# etf_pwr.net
KiCad netlist of a schematic drawn in Altium Designer
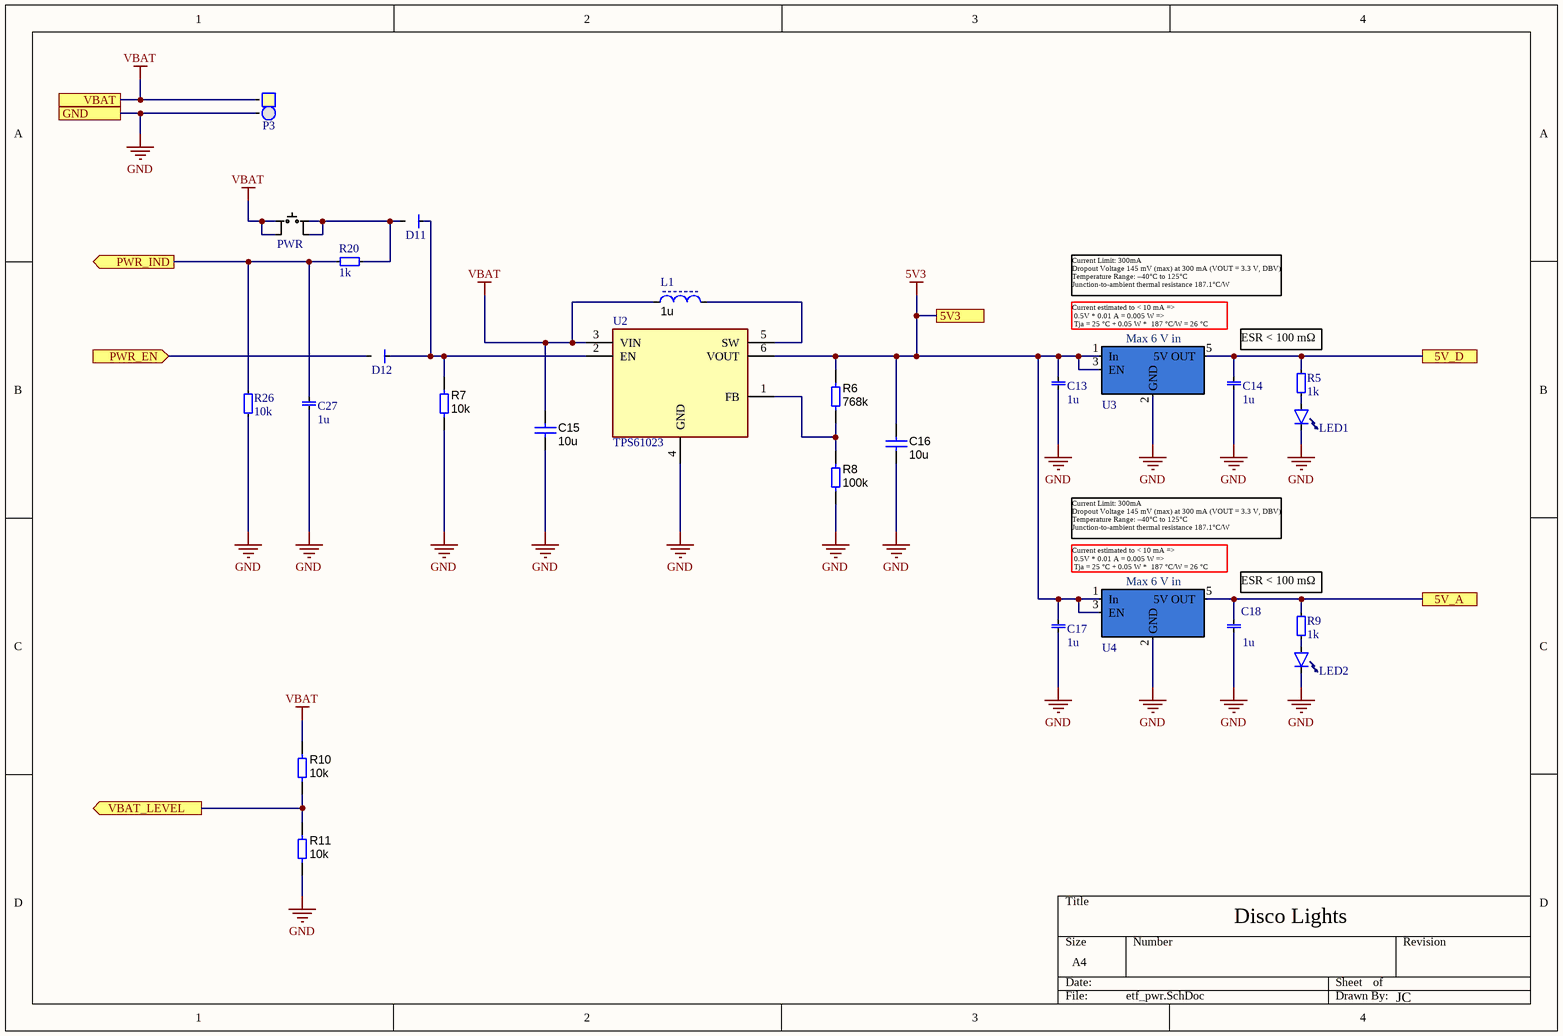
[diagram p0: etf_pwr.SchDoc]

(export (version "E")
  (design (tool "Eeschema 10.0.6"))
  (components
    (comp (ref "C13")
      (value "1u")
      (footprint "0603 cap")
      (fields
        (field (name "JLCPCB PART #") "C77386")
        (field (name "MANUFACTURER PART NUMBER") "GRM188R61H105KAALD")
        (field (name "Comment") "0603, capacitor")
      )
      (libsource (lib "jclib") (part "0603, capacitor"))
    )
    (comp (ref "C14")
      (value "1u")
      (footprint "0603 cap")
      (fields
        (field (name "JLCPCB PART #") "C77386")
        (field (name "MANUFACTURER PART NUMBER") "GRM188R61H105KAALD")
        (field (name "Comment") "0603, capacitor")
      )
      (libsource (lib "jclib") (part "0603, capacitor"))
    )
    (comp (ref "C15")
      (value "10u")
      (footprint "1206_180")
      (fields
        (field (name "JLCPCB PART #") "C342827")
        (field (name "MANUFACTURER PART NUMBER") "C3216X7R1C106KT000N")
        (field (name "Comment") "CAP, 1206")
      )
      (libsource (lib "urad") (part "CAP, 1206"))
    )
    (comp (ref "C16")
      (value "10u")
      (footprint "1206_180")
      (fields
        (field (name "JLCPCB PART #") "C342827")
        (field (name "MANUFACTURER PART NUMBER") "C3216X7R1C106KT000N")
        (field (name "Comment") "CAP, 1206")
      )
      (libsource (lib "urad") (part "CAP, 1206"))
    )
    (comp (ref "C17")
      (value "1u")
      (footprint "0603 cap")
      (fields
        (field (name "JLCPCB PART #") "C77386")
        (field (name "MANUFACTURER PART NUMBER") "GRM188R61H105KAALD")
        (field (name "Comment") "0603, capacitor")
      )
      (libsource (lib "jclib") (part "0603, capacitor"))
    )
    (comp (ref "C18")
      (value "1u")
      (footprint "0603 cap")
      (fields
        (field (name "JLCPCB PART #") "C77386")
        (field (name "MANUFACTURER PART NUMBER") "GRM188R61H105KAALD")
        (field (name "Comment") "0603, capacitor")
      )
      (libsource (lib "jclib") (part "0603, capacitor"))
    )
    (comp (ref "C27")
      (value "1u")
      (footprint "0603 cap")
      (fields
        (field (name "JLCPCB PART #") "C77386")
        (field (name "MANUFACTURER PART NUMBER") "GRM188R61H105KAALD")
        (field (name "Comment") "0603, capacitor")
      )
      (libsource (lib "jclib") (part "0603, capacitor"))
    )
    (comp (ref "D11")
      (value "Diode, SMD")
      (footprint "SOD323")
      (fields (field (name "JLCPCB PART #") "C117941") (field (name "MANUFACTURER PART NUMBER") "BAT760,115"))
      (libsource (lib "jclib") (part "Diode, SMD"))
    )
    (comp (ref "D12")
      (value "Diode, SMD")
      (footprint "SOD323")
      (fields (field (name "JLCPCB PART #") "C117941") (field (name "MANUFACTURER PART NUMBER") "BAT760,115"))
      (libsource (lib "jclib") (part "Diode, SMD"))
    )
    (comp (ref "L1")
      (value "1u")
      (footprint "XEL4030-102MEC")
      (description "Shielded Power Inductor with Ferrite Core")
      (fields
        (field (name "JLCPCB PART #") "C19947630")
        (field (name "MANUFACTURER PART NUMBER") "SRN4018BTA-1R0Y")
      )
      (libsource (lib "urad") (part "Inductor, 1616"))
    )
    (comp (ref "LED1")
      (value "0805, LED")
      (footprint "0805_led")
      (fields (field (name "JLCPCB PART #") "C2295") (field (name "MANUFACTURER PART NUMBER") "KP-2012SURCK"))
      (libsource (lib "jclib") (part "0805, LED"))
    )
    (comp (ref "LED2")
      (value "0805, LED")
      (footprint "0805_led")
      (fields (field (name "JLCPCB PART #") "C2295") (field (name "MANUFACTURER PART NUMBER") "KP-2012SURCK"))
      (libsource (lib "jclib") (part "0805, LED"))
    )
    (comp (ref "P3")
      (value "1x2 Pin Header")
      (footprint "padtwo_L")
      (description "2.54 mm, TH")
      (libsource (lib "jclib") (part "1x2 Pin Header"))
    )
    (comp (ref "PWR")
      (value "Tactile Button")
      (footprint "SW_TS02-66-150-BK-160-LCR-D")
      (description "Tactile Switch Small Low")
      (libsource (lib "urad") (part "TacButton TH"))
    )
    (comp (ref "R5")
      (value "1k")
      (footprint "0603")
      (fields
        (field (name "JLCPCB PART #") "C21190")
        (field (name "MANUFACTURER PART NUMBER") "CR0603-FX-1001ELF")
        (field (name "Comment") "0603, resistor")
      )
      (libsource (lib "jclib") (part "0603, resistor"))
    )
    (comp (ref "R6")
      (value "768k")
      (footprint "0603")
      (fields
        (field (name "JLCPCB PART #") "C2933258")
        (field (name "MANUFACTURER PART NUMBER") "CR0603F768KP05Z")
        (field (name "Comment") "RES, 0603")
      )
      (libsource (lib "urad") (part "RES, 0603"))
    )
    (comp (ref "R7")
      (value "10k")
      (footprint "0603")
      (fields
        (field (name "JLCPCB PART #") "C98220")
        (field (name "MANUFACTURER PART NUMBER") "RC0603FR-0710KL")
        (field (name "Comment") "RES, 0603")
      )
      (libsource (lib "urad") (part "RES, 0603"))
    )
    (comp (ref "R8")
      (value "100k")
      (footprint "0603")
      (fields
        (field (name "JLCPCB PART #") "C14675")
        (field (name "MANUFACTURER PART NUMBER") "RC0603FR-07100KL")
        (field (name "Comment") "RES, 0603")
      )
      (libsource (lib "urad") (part "RES, 0603"))
    )
    (comp (ref "R9")
      (value "1k")
      (footprint "0603")
      (fields
        (field (name "JLCPCB PART #") "C21190")
        (field (name "MANUFACTURER PART NUMBER") "CR0603-FX-1001ELF")
        (field (name "Comment") "0603, resistor")
      )
      (libsource (lib "jclib") (part "0603, resistor"))
    )
    (comp (ref "R10")
      (value "10k")
      (footprint "0603")
      (fields
        (field (name "JLCPCB PART #") "C98220")
        (field (name "MANUFACTURER PART NUMBER") "RC0603FR-0710KL")
        (field (name "Comment") "RES, 0603")
      )
      (libsource (lib "urad") (part "RES, 0603"))
    )
    (comp (ref "R11")
      (value "10k")
      (footprint "0603")
      (fields
        (field (name "JLCPCB PART #") "C98220")
        (field (name "MANUFACTURER PART NUMBER") "RC0603FR-0710KL")
        (field (name "Comment") "RES, 0603")
      )
      (libsource (lib "urad") (part "RES, 0603"))
    )
    (comp (ref "R20")
      (value "1k")
      (footprint "0603")
      (fields
        (field (name "JLCPCB PART #") "C21190")
        (field (name "MANUFACTURER PART NUMBER") "CR0603-FX-1001ELF")
        (field (name "Comment") "0603, resistor")
      )
      (libsource (lib "jclib") (part "0603, resistor"))
    )
    (comp (ref "R26")
      (value "10k")
      (footprint "0603")
      (fields
        (field (name "JLCPCB PART #") "C98220")
        (field (name "MANUFACTURER PART NUMBER") "RC0603FR-0710KL")
        (field (name "Comment") "0603, resistor")
      )
      (libsource (lib "jclib") (part "0603, resistor"))
    )
    (comp (ref "U2")
      (value "TPS61023")
      (footprint "SOT50P160X60-6N")
      (description "TPS61023 3.7-A Boost Converter with 0.5-V Ultra-low Input Voltage")
      (fields
        (field (name "JLCPCB PART #") "C919459")
        (field (name "MANUFACTURER PART NUMBER") "TPS61023DRLR")
      )
      (libsource (lib "urad") (part "TPS61023"))
    )
    (comp (ref "U3")
      (value "TPS7A20")
      (footprint "SOT23-5")
      (description "5V and 300-mA, Ultra-Low-Noise, Low-IQ, High PSRR LDO")
      (fields
        (field (name "JLCPCB PART #") "C2873627")
        (field (name "MANUFACTURER PART NUMBER") "TPS7A2045PDBVR")
      )
      (libsource (lib "jclib") (part "TPS7A20"))
    )
    (comp (ref "U4")
      (value "TPS7A20")
      (footprint "SOT23-5")
      (description "5V and 300-mA, Ultra-Low-Noise, Low-IQ, High PSRR LDO")
      (fields
        (field (name "JLCPCB PART #") "C2873627")
        (field (name "MANUFACTURER PART NUMBER") "TPS7A2045PDBVR")
      )
      (libsource (lib "jclib") (part "TPS7A20"))
    )
  )
  (nets
    (net (code "1") (name "/5V_A") (class "Default")
      (node (ref "C18") (pin "1") (pinfunction "1_1") (pintype "passive"))
      (node (ref "R9") (pin "1") (pinfunction "1_1") (pintype "passive"))
      (node (ref "U4") (pin "5") (pinfunction "5V_OUT_5") (pintype "passive"))
    )
    (net (code "2") (name "/5V_D") (class "Default")
      (node (ref "C14") (pin "1") (pinfunction "1_1") (pintype "passive"))
      (node (ref "R5") (pin "1") (pinfunction "1_1") (pintype "passive"))
      (node (ref "U3") (pin "5") (pinfunction "5V_OUT_5") (pintype "passive"))
    )
    (net (code "3") (name "/PWR_EN") (class "Default")
      (node (ref "D12") (pin "2") (pinfunction "2_2") (pintype "passive"))
    )
    (net (code "4") (name "/PWR_IND") (class "Default")
      (node (ref "C27") (pin "1") (pinfunction "1_1") (pintype "passive"))
      (node (ref "R20") (pin "0") (pinfunction "0_0") (pintype "passive"))
      (node (ref "R26") (pin "1") (pinfunction "1_1") (pintype "passive"))
    )
    (net (code "5") (name "/VBAT_LEVEL") (class "Default")
      (node (ref "R10") (pin "1") (pinfunction "1_1") (pintype "passive"))
      (node (ref "R11") (pin "2") (pinfunction "2_2") (pintype "passive"))
    )
    (net (code "6") (name "5V3") (class "Default")
      (node (ref "C13") (pin "1") (pinfunction "1_1") (pintype "passive"))
      (node (ref "C16") (pin "1") (pinfunction "1_1") (pintype "passive"))
      (node (ref "C17") (pin "1") (pinfunction "1_1") (pintype "passive"))
      (node (ref "R6") (pin "2") (pinfunction "2_2") (pintype "passive"))
      (node (ref "U2") (pin "6") (pinfunction "VOUT_6") (pintype "passive"))
      (node (ref "U3") (pin "1") (pinfunction "In_1") (pintype "passive"))
      (node (ref "U3") (pin "3") (pinfunction "EN_3") (pintype "passive"))
      (node (ref "U4") (pin "1") (pinfunction "In_1") (pintype "passive"))
      (node (ref "U4") (pin "3") (pinfunction "EN_3") (pintype "passive"))
    )
    (net (code "7") (name "GND") (class "Default")
      (node (ref "C13") (pin "0") (pinfunction "0_0") (pintype "passive"))
      (node (ref "C14") (pin "0") (pinfunction "0_0") (pintype "passive"))
      (node (ref "C15") (pin "2") (pinfunction "2_2") (pintype "passive"))
      (node (ref "C16") (pin "2") (pinfunction "2_2") (pintype "passive"))
      (node (ref "C17") (pin "0") (pinfunction "0_0") (pintype "passive"))
      (node (ref "C18") (pin "0") (pinfunction "0_0") (pintype "passive"))
      (node (ref "C27") (pin "0") (pinfunction "0_0") (pintype "passive"))
      (node (ref "LED1") (pin "0") (pinfunction "Cathode_0") (pintype "passive"))
      (node (ref "LED2") (pin "0") (pinfunction "Cathode_0") (pintype "passive"))
      (node (ref "P3") (pin "2") (pinfunction "2_2") (pintype "passive"))
      (node (ref "R11") (pin "1") (pinfunction "1_1") (pintype "passive"))
      (node (ref "R26") (pin "0") (pinfunction "0_0") (pintype "passive"))
      (node (ref "R7") (pin "1") (pinfunction "1_1") (pintype "passive"))
      (node (ref "R8") (pin "1") (pinfunction "1_1") (pintype "passive"))
      (node (ref "U2") (pin "4") (pinfunction "GND_4") (pintype "power_in"))
      (node (ref "U3") (pin "2") (pinfunction "GND_2") (pintype "passive"))
      (node (ref "U4") (pin "2") (pinfunction "GND_2") (pintype "passive"))
    )
    (net (code "8") (name "Net-(D11-Pad2)") (class "Default")
      (node (ref "D11") (pin "2") (pinfunction "2_2") (pintype "passive"))
      (node (ref "PWR") (pin "1") (pinfunction "1_1") (pintype "passive"))
      (node (ref "PWR") (pin "2") (pinfunction "2_2") (pintype "passive"))
      (node (ref "R20") (pin "1") (pinfunction "1_1") (pintype "passive"))
    )
    (net (code "9") (name "Net-(LED1-Pad1)") (class "Default")
      (node (ref "LED1") (pin "1") (pinfunction "1_1") (pintype "passive"))
      (node (ref "R5") (pin "0") (pinfunction "0_0") (pintype "passive"))
    )
    (net (code "10") (name "Net-(LED2-Pad1)") (class "Default")
      (node (ref "LED2") (pin "1") (pinfunction "1_1") (pintype "passive"))
      (node (ref "R9") (pin "0") (pinfunction "0_0") (pintype "passive"))
    )
    (net (code "11") (name "Net-(U2-EN)") (class "Default")
      (node (ref "D11") (pin "1") (pinfunction "1_1") (pintype "passive"))
      (node (ref "D12") (pin "1") (pinfunction "1_1") (pintype "passive"))
      (node (ref "R7") (pin "2") (pinfunction "2_2") (pintype "passive"))
      (node (ref "U2") (pin "2") (pinfunction "EN_2") (pintype "passive"))
    )
    (net (code "12") (name "Net-(U2-FB)") (class "Default")
      (node (ref "R6") (pin "1") (pinfunction "1_1") (pintype "passive"))
      (node (ref "R8") (pin "2") (pinfunction "2_2") (pintype "passive"))
      (node (ref "U2") (pin "1") (pinfunction "FB_1") (pintype "passive"))
    )
    (net (code "13") (name "Net-(U2-SW)") (class "Default")
      (node (ref "L1") (pin "1") (pinfunction "1_1") (pintype "passive"))
      (node (ref "U2") (pin "5") (pinfunction "SW_5") (pintype "passive"))
    )
    (net (code "14") (name "VBAT") (class "Default")
      (node (ref "C15") (pin "1") (pinfunction "1_1") (pintype "passive"))
      (node (ref "L1") (pin "2") (pinfunction "2_2") (pintype "passive"))
      (node (ref "P3") (pin "1") (pinfunction "1_1") (pintype "passive"))
      (node (ref "PWR") (pin "3") (pinfunction "3_3") (pintype "passive"))
      (node (ref "PWR") (pin "4") (pinfunction "4_4") (pintype "passive"))
      (node (ref "R10") (pin "2") (pinfunction "2_2") (pintype "passive"))
      (node (ref "U2") (pin "3") (pinfunction "VIN_3") (pintype "passive"))
    )
  )
)
